# oled.net
KiCad netlist of a schematic drawn in Altium Designer
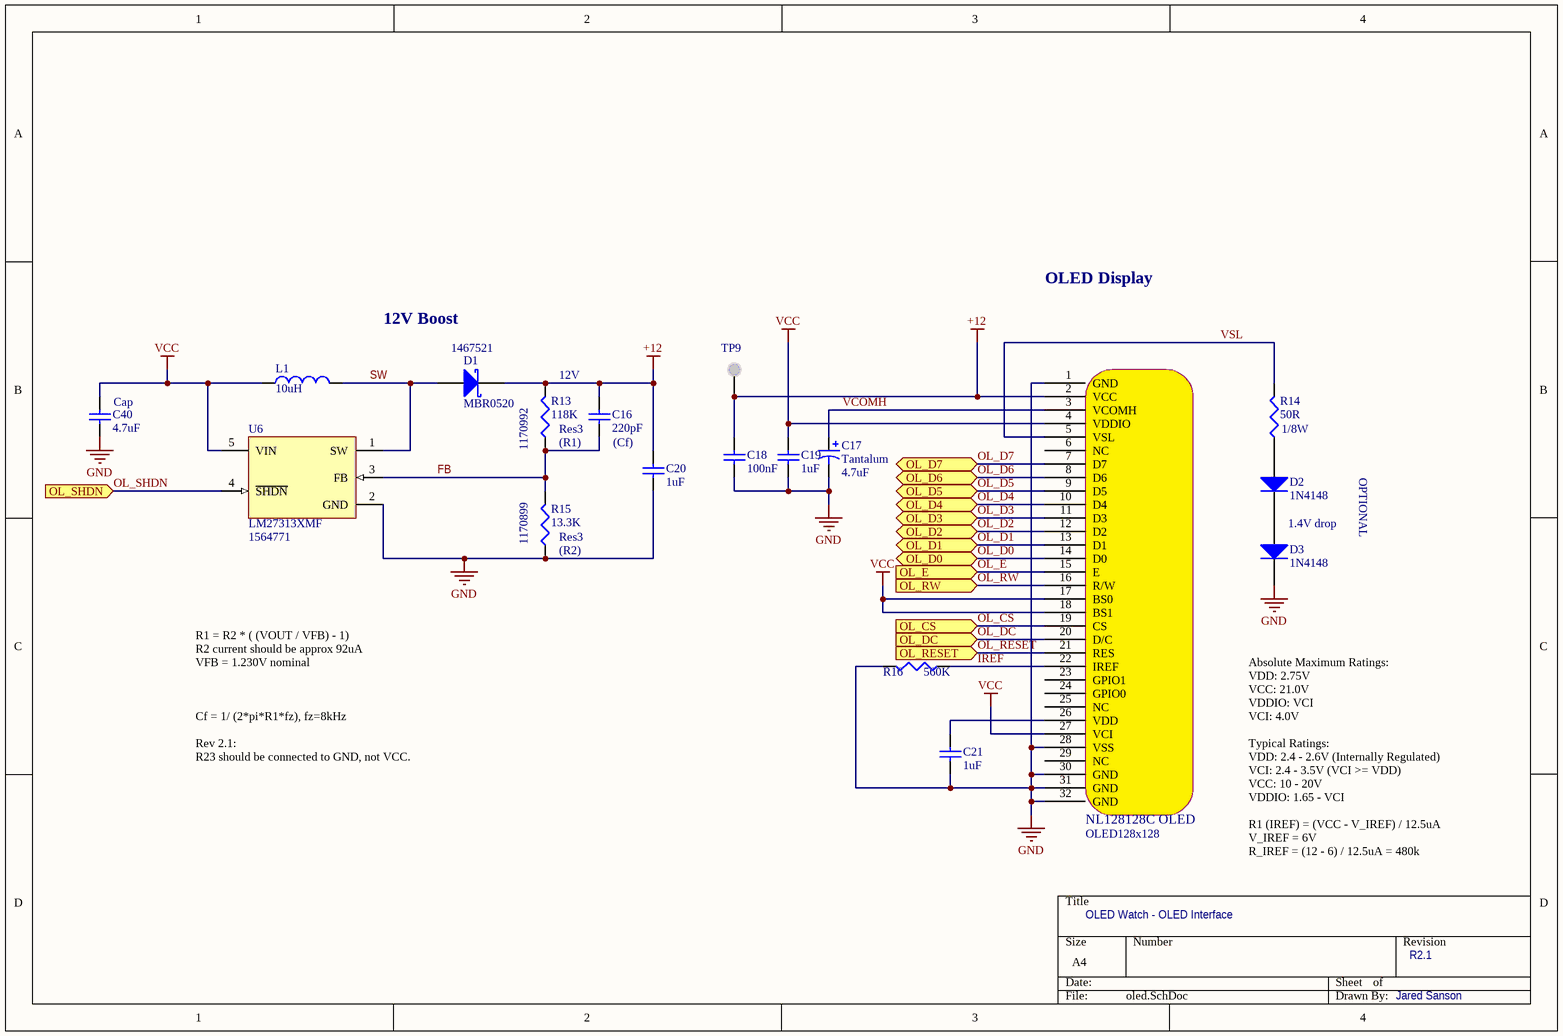
[diagram p0: oled.SchDoc]

(export (version "E")
  (design (tool "Eeschema 10.0.6"))
  (components
    (comp (ref "C16")
      (value "220pF")
      (footprint "0603C")
      (description "Capacitor")
      (fields
        (field (name "VARIABLE") "(Cf)")
        (field (name "Comment") "Cap")
        (field (name "PUBLISHER") "Altium Limited")
      )
      (libsource (lib "Miscellaneous Devices") (part "Cap"))
    )
    (comp (ref "C17")
      (value "Tantalum")
      (footprint "0805C")
      (description "Polarized Capacitor (Radial)")
      (fields (field (name "ALTIUM_VALUE") "4.7uF") (field (name "PUBLISHER") "Altium Limited"))
      (libsource (lib "Miscellaneous Devices") (part "Cap Pol1"))
    )
    (comp (ref "C18")
      (value "100nF")
      (footprint "0603C")
      (description "Capacitor")
      (fields (field (name "Comment") "Cap") (field (name "PUBLISHER") "Altium Limited"))
      (libsource (lib "Miscellaneous Devices") (part "Cap"))
    )
    (comp (ref "C19")
      (value "1uF")
      (footprint "0603C")
      (description "Capacitor")
      (fields (field (name "Comment") "Cap") (field (name "PUBLISHER") "Altium Limited"))
      (libsource (lib "Miscellaneous Devices") (part "Cap"))
    )
    (comp (ref "C20")
      (value "1uF")
      (footprint "0805C")
      (description "Capacitor")
      (fields (field (name "Comment") "Cap") (field (name "PUBLISHER") "Altium Limited"))
      (libsource (lib "Miscellaneous Devices") (part "Cap"))
    )
    (comp (ref "C21")
      (value "1uF")
      (footprint "0805C")
      (description "Capacitor")
      (fields (field (name "Comment") "Cap") (field (name "PUBLISHER") "Altium Limited"))
      (libsource (lib "Miscellaneous Devices") (part "Cap"))
    )
    (comp (ref "C40")
      (value "Cap")
      (footprint "0805C")
      (description "Capacitor")
      (fields (field (name "ALTIUM_VALUE") "4.7uF") (field (name "PUBLISHER") "Altium Limited"))
      (libsource (lib "Miscellaneous Devices") (part "Cap"))
    )
    (comp (ref "D1")
      (value "MBR0520")
      (footprint "0603D")
      (description "Schottky Diode")
      (fields (field (name "SUPPLIER PART NUMBER 1") "1467521") (field (name "PUBLISHER") "Altium Limited"))
      (libsource (lib "Miscellaneous Devices") (part "D Schottky"))
    )
    (comp (ref "D2")
      (value "1N4148")
      (footprint "0603D")
      (description "Default Diode")
      (fields (field (name "PUBLISHER") "Altium Limited"))
      (libsource (lib "Miscellaneous Devices") (part "Diode"))
    )
    (comp (ref "D3")
      (value "1N4148")
      (footprint "0603D")
      (description "Default Diode")
      (fields (field (name "PUBLISHER") "Altium Limited"))
      (libsource (lib "Miscellaneous Devices") (part "Diode"))
    )
    (comp (ref "L1")
      (value "10uH")
      (footprint "INDC3225N")
      (description "Inductor")
      (fields (field (name "PUBLISHER") "Altium Limited"))
      (libsource (lib "Miscellaneous Devices") (part "Inductor"))
    )
    (comp (ref "OLED128x128")
      (value "OLED128x128")
      (footprint "OLED128X128")
      (description "OLED")
      (libsource (lib "数字单片机芯片 元器件库") (part "OLED128x128"))
    )
    (comp (ref "R13")
      (value "Res3")
      (footprint "0603R")
      (description "Resistor")
      (fields
        (field (name "ALTIUM_VALUE") "118K")
        (field (name "VARIABLE") "(R1)")
        (field (name "SUPPLIER PART NUMBER 1") "1170992")
        (field (name "PUBLISHER") "Altium Limited")
      )
      (libsource (lib "Miscellaneous Devices") (part "Res3"))
    )
    (comp (ref "R14")
      (value "50R")
      (footprint "0603R")
      (description "Resistor")
      (fields (field (name "Comment") "Res3") (field (name "PUBLISHER") "Altium Limited"))
      (libsource (lib "Miscellaneous Devices") (part "Res3"))
    )
    (comp (ref "R15")
      (value "Res3")
      (footprint "0603R")
      (description "Resistor")
      (fields
        (field (name "ALTIUM_VALUE") "13.3K")
        (field (name "VARIABLE") "(R2)")
        (field (name "SUPPLIER PART NUMBER 1") "1170899")
        (field (name "PUBLISHER") "Altium Limited")
      )
      (libsource (lib "Miscellaneous Devices") (part "Res3"))
    )
    (comp (ref "R16")
      (value "560K")
      (footprint "0603R")
      (description "Resistor")
      (fields (field (name "Comment") "Res3") (field (name "PUBLISHER") "Altium Limited"))
      (libsource (lib "Miscellaneous Devices") (part "Res3"))
    )
    (comp (ref "TP9")
      (value "+12")
      (footprint "TESTPOINT_TOP")
      (description "Test Point")
      (libsource (lib "JLib") (part "TestPoint"))
    )
    (comp (ref "U6")
      (value "LM27313XMF")
      (footprint "MF05A_N")
      (description "1.6 MHz Boost Converter With 30V Internal FET Switch in SOT-23")
      (fields
        (field (name "MANUFACTURER") "National Semiconductor")
        (field (name "DIGIKEYPARTNUMBER") "LM27313XMFCT-ND")
        (field (name "SUPPLIER PART NUMBER 1") "1564771")
        (field (name "PUBLISHER") "Altium Limited")
      )
      (libsource (lib "NSC Switcher") (part "LM27313XMF"))
    )
  )
  (nets
    (net (code "1") (name "+12") (class "Default")
      (node (ref "C16") (pin "1") (pinfunction "1_1") (pintype "passive"))
      (node (ref "C18") (pin "1") (pinfunction "1_1") (pintype "passive"))
      (node (ref "C20") (pin "1") (pinfunction "1_1") (pintype "passive"))
      (node (ref "D1") (pin "2") (pinfunction "K_2") (pintype "passive"))
      (node (ref "OLED128x128") (pin "2") (pinfunction "VCC_2") (pintype "passive"))
      (node (ref "R13") (pin "2") (pinfunction "2_2") (pintype "passive"))
      (node (ref "TP9") (pin "1") (pinfunction "TP_1") (pintype "passive"))
    )
    (net (code "2") (name "/FB") (class "Default")
      (node (ref "C16") (pin "2") (pinfunction "2_2") (pintype "passive"))
      (node (ref "R13") (pin "1") (pinfunction "1_1") (pintype "passive"))
      (node (ref "R15") (pin "2") (pinfunction "2_2") (pintype "passive"))
      (node (ref "U6") (pin "3") (pinfunction "FB_3") (pintype "input"))
    )
    (net (code "3") (name "/IREF") (class "Default")
      (node (ref "OLED128x128") (pin "22") (pinfunction "IREF_22") (pintype "passive"))
      (node (ref "R16") (pin "1") (pinfunction "1_1") (pintype "passive"))
    )
    (net (code "4") (name "/OL_CS") (class "Default")
      (node (ref "OLED128x128") (pin "19") (pinfunction "CS_19") (pintype "passive"))
    )
    (net (code "5") (name "/OL_D0") (class "Default")
      (node (ref "OLED128x128") (pin "14") (pinfunction "D0_14") (pintype "passive"))
    )
    (net (code "6") (name "/OL_D1") (class "Default")
      (node (ref "OLED128x128") (pin "13") (pinfunction "D1_13") (pintype "passive"))
    )
    (net (code "7") (name "/OL_D2") (class "Default")
      (node (ref "OLED128x128") (pin "12") (pinfunction "D2_12") (pintype "passive"))
    )
    (net (code "8") (name "/OL_D3") (class "Default")
      (node (ref "OLED128x128") (pin "11") (pinfunction "D3_11") (pintype "passive"))
    )
    (net (code "9") (name "/OL_D4") (class "Default")
      (node (ref "OLED128x128") (pin "10") (pinfunction "D4_10") (pintype "passive"))
    )
    (net (code "10") (name "/OL_D5") (class "Default")
      (node (ref "OLED128x128") (pin "9") (pinfunction "D5_9") (pintype "passive"))
    )
    (net (code "11") (name "/OL_D6") (class "Default")
      (node (ref "OLED128x128") (pin "8") (pinfunction "D6_8") (pintype "passive"))
    )
    (net (code "12") (name "/OL_D7") (class "Default")
      (node (ref "OLED128x128") (pin "7") (pinfunction "D7_7") (pintype "passive"))
    )
    (net (code "13") (name "/OL_DC") (class "Default")
      (node (ref "OLED128x128") (pin "20") (pinfunction "D/C_20") (pintype "passive"))
    )
    (net (code "14") (name "/OL_E") (class "Default")
      (node (ref "OLED128x128") (pin "15") (pinfunction "E_15") (pintype "passive"))
    )
    (net (code "15") (name "/OL_RESET") (class "Default")
      (node (ref "OLED128x128") (pin "21") (pinfunction "RES_21") (pintype "passive"))
    )
    (net (code "16") (name "/OL_RW") (class "Default")
      (node (ref "OLED128x128") (pin "16") (pinfunction "R/W_16") (pintype "passive"))
    )
    (net (code "17") (name "/OL_SHDN") (class "Default")
      (node (ref "U6") (pin "4") (pinfunction "~{SHDN}_4") (pintype "input"))
    )
    (net (code "18") (name "/SW") (class "Default")
      (node (ref "D1") (pin "1") (pinfunction "A_1") (pintype "passive"))
      (node (ref "L1") (pin "2") (pinfunction "2_2") (pintype "passive"))
      (node (ref "U6") (pin "1") (pinfunction "SW_1") (pintype "power_in"))
    )
    (net (code "19") (name "/VCOMH") (class "Default")
      (node (ref "C17") (pin "1") (pinfunction "1_1") (pintype "passive"))
      (node (ref "OLED128x128") (pin "3") (pinfunction "VCOMH_3") (pintype "passive"))
    )
    (net (code "20") (name "/VSL") (class "Default")
      (node (ref "OLED128x128") (pin "5") (pinfunction "VSL_5") (pintype "passive"))
      (node (ref "R14") (pin "2") (pinfunction "2_2") (pintype "passive"))
    )
    (net (code "21") (name "GND") (class "Default")
      (node (ref "C17") (pin "2") (pinfunction "2_2") (pintype "passive"))
      (node (ref "C18") (pin "2") (pinfunction "2_2") (pintype "passive"))
      (node (ref "C19") (pin "2") (pinfunction "2_2") (pintype "passive"))
      (node (ref "C20") (pin "2") (pinfunction "2_2") (pintype "passive"))
      (node (ref "C21") (pin "2") (pinfunction "2_2") (pintype "passive"))
      (node (ref "C40") (pin "2") (pinfunction "2_2") (pintype "passive"))
      (node (ref "D3") (pin "2") (pinfunction "K_2") (pintype "passive"))
      (node (ref "OLED128x128") (pin "1") (pinfunction "GND_1") (pintype "power_in"))
      (node (ref "OLED128x128") (pin "28") (pinfunction "VSS_28") (pintype "passive"))
      (node (ref "OLED128x128") (pin "30") (pinfunction "GND_30") (pintype "passive"))
      (node (ref "OLED128x128") (pin "31") (pinfunction "GND_31") (pintype "passive"))
      (node (ref "OLED128x128") (pin "32") (pinfunction "GND_32") (pintype "passive"))
      (node (ref "R15") (pin "1") (pinfunction "1_1") (pintype "passive"))
      (node (ref "R16") (pin "2") (pinfunction "2_2") (pintype "passive"))
      (node (ref "U6") (pin "2") (pinfunction "GND_2") (pintype "power_in"))
    )
    (net (code "22") (name "Net-(D2-A)") (class "Default")
      (node (ref "D2") (pin "1") (pinfunction "A_1") (pintype "passive"))
      (node (ref "R14") (pin "1") (pinfunction "1_1") (pintype "passive"))
    )
    (net (code "23") (name "Net-(D2-K)") (class "Default")
      (node (ref "D2") (pin "2") (pinfunction "K_2") (pintype "passive"))
      (node (ref "D3") (pin "1") (pinfunction "A_1") (pintype "passive"))
    )
    (net (code "24") (name "Net-(OLED128x128-VDD)") (class "Default")
      (node (ref "C21") (pin "1") (pinfunction "1_1") (pintype "passive"))
      (node (ref "OLED128x128") (pin "26") (pinfunction "VDD_26") (pintype "passive"))
    )
    (net (code "25") (name "VCC") (class "Default")
      (node (ref "C19") (pin "1") (pinfunction "1_1") (pintype "passive"))
      (node (ref "C40") (pin "1") (pinfunction "1_1") (pintype "passive"))
      (node (ref "L1") (pin "1") (pinfunction "1_1") (pintype "passive"))
      (node (ref "OLED128x128") (pin "17") (pinfunction "BS0_17") (pintype "passive"))
      (node (ref "OLED128x128") (pin "18") (pinfunction "BS1_18") (pintype "passive"))
      (node (ref "OLED128x128") (pin "27") (pinfunction "VCI_27") (pintype "passive"))
      (node (ref "OLED128x128") (pin "4") (pinfunction "VDDIO_4") (pintype "passive"))
      (node (ref "U6") (pin "5") (pinfunction "VIN_5") (pintype "power_in"))
    )
    (net (code "26") (name "unconnected-(OLED128x128-GPIO0-Pad24)") (class "Default")
      (node (ref "OLED128x128") (pin "24") (pinfunction "GPIO0_24") (pintype "passive"))
    )
    (net (code "27") (name "unconnected-(OLED128x128-GPIO1-Pad23)") (class "Default")
      (node (ref "OLED128x128") (pin "23") (pinfunction "GPIO1_23") (pintype "passive"))
    )
    (net (code "28") (name "unconnected-(OLED128x128-NC-Pad6)") (class "Default")
      (node (ref "OLED128x128") (pin "6") (pinfunction "NC_6") (pintype "passive"))
    )
    (net (code "29") (name "unconnected-(OLED128x128-NC-Pad25)") (class "Default")
      (node (ref "OLED128x128") (pin "25") (pinfunction "NC_25") (pintype "passive"))
    )
    (net (code "30") (name "unconnected-(OLED128x128-NC-Pad29)") (class "Default")
      (node (ref "OLED128x128") (pin "29") (pinfunction "NC_29") (pintype "passive"))
    )
  )
)
